# Prog_Adaptor.net
KiCad netlist of a schematic drawn in Altium Designer
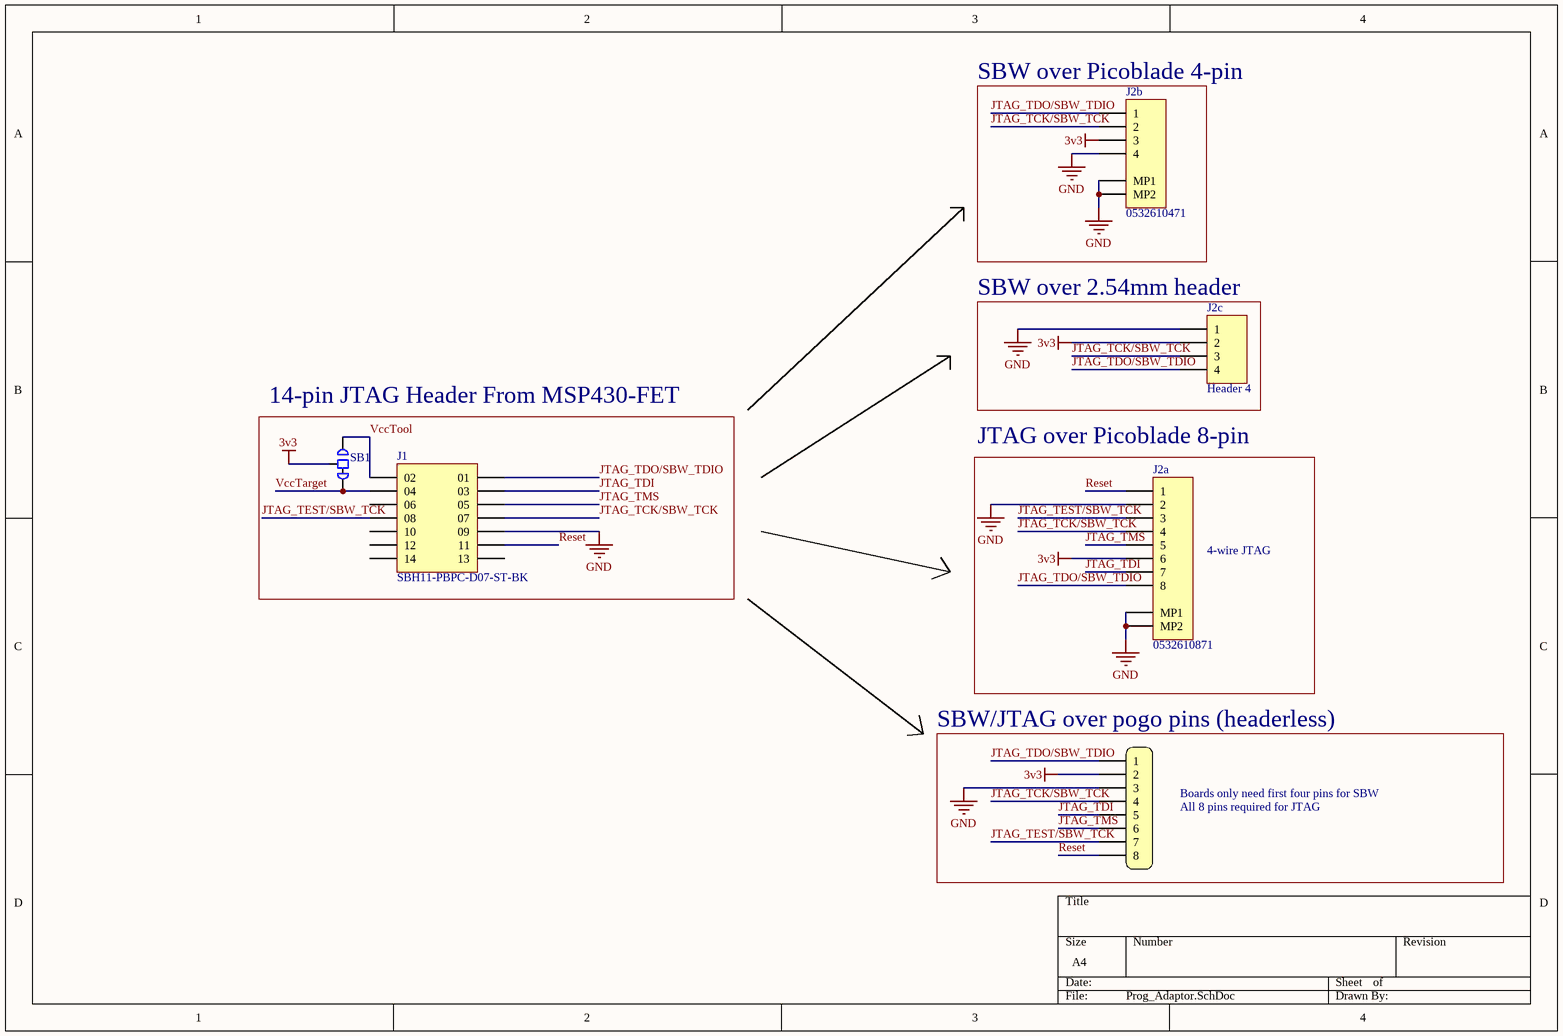
[diagram p0: Prog_Adaptor.SchDoc]

(export (version "E")
  (design (tool "Eeschema 10.0.6"))
  (components
    (comp (ref "J1")
      (value "SBH11-PBPC-D07-ST-BK")
      (footprint "APSS Prototype Parts:SBH11-PBPC-D07-ST-BK")
      (description "14-pin JTAG Male Header")
      (libsource (lib "APSS Prototype Parts") (part "SBH11-PBPC-D07-ST-BK"))
    )
    (comp (ref "J2a")
      (value "0532610871")
      (footprint "APSS Prototype Parts:MOLEX_0532610871")
      (description "Header - Picoblade 08-pin, SMT, RA")
      (fields (field (name "MF PART NO.") "0532610871"))
      (libsource (lib "APSS Prototype Parts") (part "0532610871"))
    )
    (comp (ref "J2b")
      (value "0532610471")
      (footprint "APSS Prototype Parts:MOLEX_0532610471")
      (description "Header - Picoblade 04-pin, SMT, RA")
      (fields (field (name "MF PART NO.") "0532610471"))
      (libsource (lib "APSS Prototype Parts") (part "0532610471"))
    )
    (comp (ref "J2c")
      (value "Header 4")
      (footprint "HDR1X4")
      (description "Header, 4-Pin")
      (fields (field (name "PUBLISHER") "Altium Limited"))
      (libsource (lib "Miscellaneous Connectors") (part "Header 4"))
    )
    (comp (ref "J2d")
      (value "*")
      (footprint "POGO_8_PIN_HEADER")
      (libsource (lib "APSS Generic Components") (part "Headerless Pogo Holes 8-pin"))
    )
    (comp (ref "SB1")
      (value "Solder Jumper 3-pin Left connected 0201")
      (footprint "Solder Bridge 3-pin Left shorted 0201")
      (libsource (lib "APSS Generic Components") (part "Solder Jumper 3-pin Normally Closed 0201"))
    )
  )
  (nets
    (net (code "1") (name "/JTAG_TCK{slash}SBW_TCK") (class "Default")
      (node (ref "J1") (pin "07") (pinfunction "07_07") (pintype "passive"))
      (node (ref "J2a") (pin "4") (pinfunction "4_4") (pintype "passive"))
      (node (ref "J2b") (pin "2") (pinfunction "2_2") (pintype "passive"))
      (node (ref "J2c") (pin "3") (pinfunction "3_3") (pintype "passive"))
      (node (ref "J2d") (pin "4") (pinfunction "4_4") (pintype "passive"))
    )
    (net (code "2") (name "/JTAG_TDI") (class "Default")
      (node (ref "J1") (pin "03") (pinfunction "03_03") (pintype "passive"))
      (node (ref "J2a") (pin "7") (pinfunction "7_7") (pintype "passive"))
      (node (ref "J2d") (pin "5") (pinfunction "5_5") (pintype "passive"))
    )
    (net (code "3") (name "/JTAG_TDO{slash}SBW_TDIO") (class "Default")
      (node (ref "J1") (pin "01") (pinfunction "01_01") (pintype "passive"))
      (node (ref "J2a") (pin "8") (pinfunction "8_8") (pintype "passive"))
      (node (ref "J2b") (pin "1") (pinfunction "1_1") (pintype "passive"))
      (node (ref "J2c") (pin "4") (pinfunction "4_4") (pintype "passive"))
      (node (ref "J2d") (pin "1") (pinfunction "1_1") (pintype "passive"))
    )
    (net (code "4") (name "/JTAG_TEST{slash}SBW_TCK") (class "Default")
      (node (ref "J1") (pin "08") (pinfunction "08_08") (pintype "passive"))
      (node (ref "J2a") (pin "3") (pinfunction "3_3") (pintype "passive"))
      (node (ref "J2d") (pin "7") (pinfunction "7_7") (pintype "passive"))
    )
    (net (code "5") (name "/JTAG_TMS") (class "Default")
      (node (ref "J1") (pin "05") (pinfunction "05_05") (pintype "passive"))
      (node (ref "J2a") (pin "5") (pinfunction "5_5") (pintype "passive"))
      (node (ref "J2d") (pin "6") (pinfunction "6_6") (pintype "passive"))
    )
    (net (code "6") (name "/Reset") (class "Default")
      (node (ref "J1") (pin "11") (pinfunction "11_11") (pintype "passive"))
      (node (ref "J2a") (pin "1") (pinfunction "1_1") (pintype "passive"))
      (node (ref "J2d") (pin "8") (pinfunction "8_8") (pintype "passive"))
    )
    (net (code "7") (name "/VccTarget") (class "Default")
      (node (ref "J1") (pin "04") (pinfunction "04_04") (pintype "passive"))
      (node (ref "SB1") (pin "2") (pinfunction "2_2") (pintype "passive"))
    )
    (net (code "8") (name "/VccTool") (class "Default")
      (node (ref "J1") (pin "02") (pinfunction "02_02") (pintype "passive"))
      (node (ref "SB1") (pin "3") (pinfunction "3_3") (pintype "passive"))
    )
    (net (code "9") (name "3v3") (class "Default")
      (node (ref "J2a") (pin "6") (pinfunction "6_6") (pintype "passive"))
      (node (ref "J2b") (pin "3") (pinfunction "3_3") (pintype "passive"))
      (node (ref "J2c") (pin "2") (pinfunction "2_2") (pintype "passive"))
      (node (ref "J2d") (pin "2") (pinfunction "2_2") (pintype "passive"))
      (node (ref "SB1") (pin "1") (pinfunction "Common_1") (pintype "passive"))
    )
    (net (code "10") (name "GND") (class "Default")
      (node (ref "J1") (pin "09") (pinfunction "09_09") (pintype "passive"))
      (node (ref "J2a") (pin "2") (pinfunction "2_2") (pintype "passive"))
      (node (ref "J2a") (pin "MP1") (pinfunction "MP1_MP1") (pintype "passive"))
      (node (ref "J2a") (pin "MP2") (pinfunction "MP2_MP2") (pintype "passive"))
      (node (ref "J2b") (pin "4") (pinfunction "4_4") (pintype "passive"))
      (node (ref "J2b") (pin "MP1") (pinfunction "MP1_MP1") (pintype "passive"))
      (node (ref "J2b") (pin "MP2") (pinfunction "MP2_MP2") (pintype "passive"))
      (node (ref "J2c") (pin "1") (pinfunction "1_1") (pintype "passive"))
      (node (ref "J2d") (pin "3") (pinfunction "3_3") (pintype "passive"))
    )
    (net (code "11") (name "unconnected-(J1-Pad06)") (class "Default")
      (node (ref "J1") (pin "06") (pinfunction "06_06") (pintype "passive"))
    )
    (net (code "12") (name "unconnected-(J1-Pad10)") (class "Default")
      (node (ref "J1") (pin "10") (pinfunction "10_10") (pintype "passive"))
    )
    (net (code "13") (name "unconnected-(J1-Pad12)") (class "Default")
      (node (ref "J1") (pin "12") (pinfunction "12_12") (pintype "passive"))
    )
    (net (code "14") (name "unconnected-(J1-Pad13)") (class "Default")
      (node (ref "J1") (pin "13") (pinfunction "13_13") (pintype "passive"))
    )
    (net (code "15") (name "unconnected-(J1-Pad14)") (class "Default")
      (node (ref "J1") (pin "14") (pinfunction "14_14") (pintype "passive"))
    )
  )
)
